# amplifier_v0001.net
KiCad netlist of a schematic drawn in EAGLE
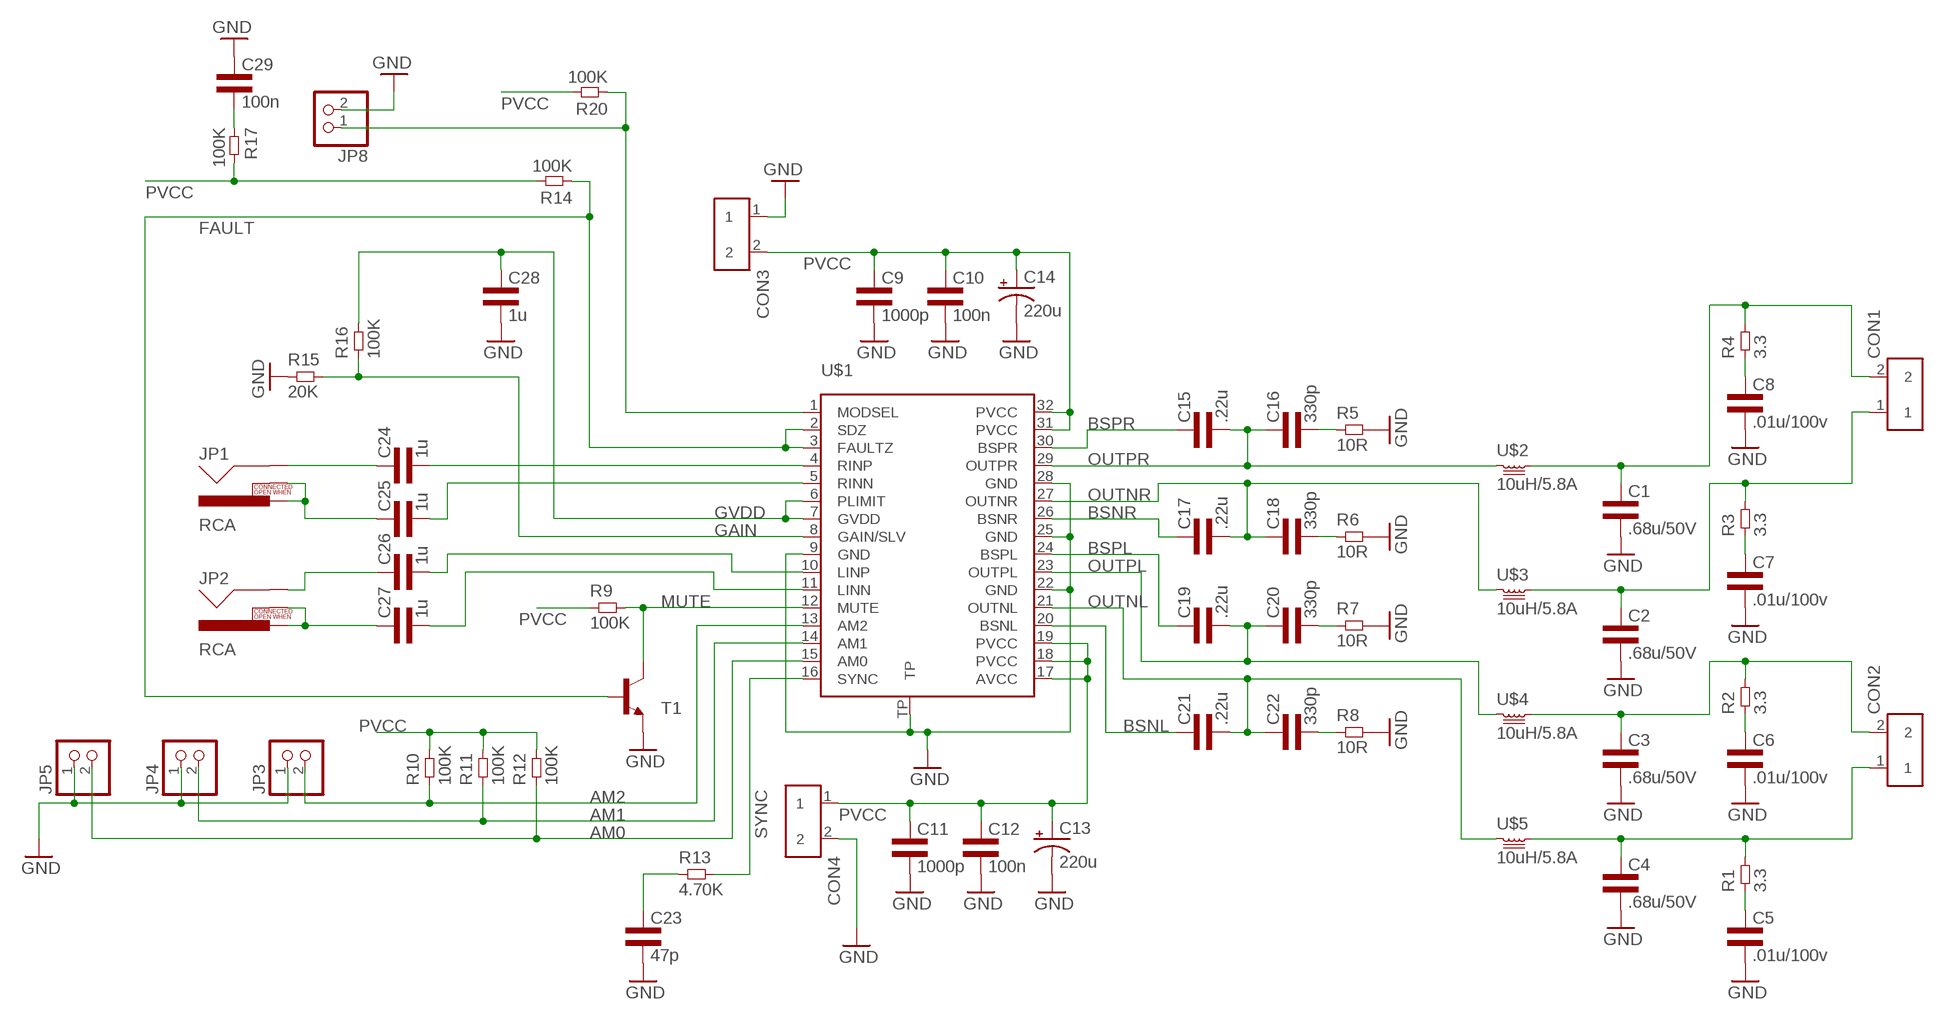
[diagram p0: schematic, sheet 1]

(export (version "E")
  (design (tool "Eeschema 10.0.6"))
  (components
    (comp (ref "C1")
      (value ".68u/50V")
      (footprint "eagle-import:1206L3")
      (libsource (lib "eagle-import") (part "CAP1206L3"))
    )
    (comp (ref "C2")
      (value ".68u/50V")
      (footprint "eagle-import:1206L3")
      (libsource (lib "eagle-import") (part "CAP1206L3"))
    )
    (comp (ref "C3")
      (value ".68u/50V")
      (footprint "eagle-import:1206L3")
      (libsource (lib "eagle-import") (part "CAP1206L3"))
    )
    (comp (ref "C4")
      (value ".68u/50V")
      (footprint "eagle-import:1206L3")
      (libsource (lib "eagle-import") (part "CAP1206L3"))
    )
    (comp (ref "C5")
      (value ".01u/100v")
      (footprint "eagle-import:0805L3")
      (libsource (lib "eagle-import") (part "CAP0805L3"))
    )
    (comp (ref "C6")
      (value ".01u/100v")
      (footprint "eagle-import:0805L3")
      (libsource (lib "eagle-import") (part "CAP0805L3"))
    )
    (comp (ref "C7")
      (value ".01u/100v")
      (footprint "eagle-import:0805L3")
      (libsource (lib "eagle-import") (part "CAP0805L3"))
    )
    (comp (ref "C8")
      (value ".01u/100v")
      (footprint "eagle-import:0805L3")
      (libsource (lib "eagle-import") (part "CAP0805L3"))
    )
    (comp (ref "C9")
      (value "1000p")
      (footprint "eagle-import:0603L3")
      (libsource (lib "eagle-import") (part "CAP0603L3"))
    )
    (comp (ref "C10")
      (value "100n")
      (footprint "eagle-import:0603L3")
      (libsource (lib "eagle-import") (part "CAP0603L3"))
    )
    (comp (ref "C11")
      (value "1000p")
      (footprint "eagle-import:0603L3")
      (libsource (lib "eagle-import") (part "CAP0603L3"))
    )
    (comp (ref "C12")
      (value "100n")
      (footprint "eagle-import:0603L3")
      (libsource (lib "eagle-import") (part "CAP0603L3"))
    )
    (comp (ref "C13")
      (value "220u")
      (footprint "eagle-import:E3,5-8")
      (libsource (lib "eagle-import") (part "CPOL-USE3.5-8"))
    )
    (comp (ref "C14")
      (value "220u")
      (footprint "eagle-import:E3,5-8")
      (libsource (lib "eagle-import") (part "CPOL-USE3.5-8"))
    )
    (comp (ref "C15")
      (value ".22u")
      (footprint "eagle-import:0603L3")
      (libsource (lib "eagle-import") (part "CAP0603L3"))
    )
    (comp (ref "C16")
      (value "330p")
      (footprint "eagle-import:0603L3")
      (libsource (lib "eagle-import") (part "CAP0603L3"))
    )
    (comp (ref "C17")
      (value ".22u")
      (footprint "eagle-import:0603L3")
      (libsource (lib "eagle-import") (part "CAP0603L3"))
    )
    (comp (ref "C18")
      (value "330p")
      (footprint "eagle-import:0603L3")
      (libsource (lib "eagle-import") (part "CAP0603L3"))
    )
    (comp (ref "C19")
      (value ".22u")
      (footprint "eagle-import:0603L3")
      (libsource (lib "eagle-import") (part "CAP0603L3"))
    )
    (comp (ref "C20")
      (value "330p")
      (footprint "eagle-import:0603L3")
      (libsource (lib "eagle-import") (part "CAP0603L3"))
    )
    (comp (ref "C21")
      (value ".22u")
      (footprint "eagle-import:0603L3")
      (libsource (lib "eagle-import") (part "CAP0603L3"))
    )
    (comp (ref "C22")
      (value "330p")
      (footprint "eagle-import:0603L3")
      (libsource (lib "eagle-import") (part "CAP0603L3"))
    )
    (comp (ref "C23")
      (value "47p")
      (footprint "eagle-import:0603L3")
      (libsource (lib "eagle-import") (part "CAP0603L3"))
    )
    (comp (ref "C24")
      (value "1u")
      (footprint "eagle-import:0603L3")
      (libsource (lib "eagle-import") (part "CAP0603L3"))
    )
    (comp (ref "C25")
      (value "1u")
      (footprint "eagle-import:0603L3")
      (libsource (lib "eagle-import") (part "CAP0603L3"))
    )
    (comp (ref "C26")
      (value "1u")
      (footprint "eagle-import:0603L3")
      (libsource (lib "eagle-import") (part "CAP0603L3"))
    )
    (comp (ref "C27")
      (value "1u")
      (footprint "eagle-import:0603L3")
      (libsource (lib "eagle-import") (part "CAP0603L3"))
    )
    (comp (ref "C28")
      (value "1u")
      (footprint "eagle-import:0603L3")
      (libsource (lib "eagle-import") (part "CAP0603L3"))
    )
    (comp (ref "C29")
      (value "100n")
      (footprint "eagle-import:0603L3")
      (libsource (lib "eagle-import") (part "CAP0603L3"))
    )
    (comp (ref "CON1")
      (value "TERM_BLOCK_2")
      (footprint "eagle-import:TERM_BLOCK_2")
      (libsource (lib "eagle-import") (part "TERM_BLOCK_2"))
    )
    (comp (ref "CON2")
      (value "TERM_BLOCK_2")
      (footprint "eagle-import:TERM_BLOCK_2")
      (libsource (lib "eagle-import") (part "TERM_BLOCK_2"))
    )
    (comp (ref "CON3")
      (value "TERM_BLOCK_2")
      (footprint "eagle-import:TERM_BLOCK_2")
      (libsource (lib "eagle-import") (part "TERM_BLOCK_2"))
    )
    (comp (ref "CON4")
      (value "TERM_BLOCK_2")
      (footprint "eagle-import:TERM_BLOCK_2")
      (libsource (lib "eagle-import") (part "TERM_BLOCK_2"))
    )
    (comp (ref "JP1")
      (value "RCA")
      (footprint "eagle-import:RCA")
      (libsource (lib "eagle-import") (part "RCA"))
    )
    (comp (ref "JP2")
      (value "RCA")
      (footprint "eagle-import:RCA")
      (libsource (lib "eagle-import") (part "RCA"))
    )
    (comp (ref "JP3")
      (value "PINHD-1X2")
      (footprint "eagle-import:1X02")
      (libsource (lib "eagle-import") (part "PINHD-1X2"))
    )
    (comp (ref "JP4")
      (value "PINHD-1X2")
      (footprint "eagle-import:1X02")
      (libsource (lib "eagle-import") (part "PINHD-1X2"))
    )
    (comp (ref "JP5")
      (value "PINHD-1X2")
      (footprint "eagle-import:1X02")
      (libsource (lib "eagle-import") (part "PINHD-1X2"))
    )
    (comp (ref "JP8")
      (value "PINHD-1X2")
      (footprint "eagle-import:1X02")
      (libsource (lib "eagle-import") (part "PINHD-1X2"))
    )
    (comp (ref "R1")
      (value "3.3")
      (footprint "eagle-import:0603L3")
      (libsource (lib "eagle-import") (part "RES0603L3"))
    )
    (comp (ref "R2")
      (value "3.3")
      (footprint "eagle-import:0603L3")
      (libsource (lib "eagle-import") (part "RES0603L3"))
    )
    (comp (ref "R3")
      (value "3.3")
      (footprint "eagle-import:0603L3")
      (libsource (lib "eagle-import") (part "RES0603L3"))
    )
    (comp (ref "R4")
      (value "3.3")
      (footprint "eagle-import:0603L3")
      (libsource (lib "eagle-import") (part "RES0603L3"))
    )
    (comp (ref "R5")
      (value "10R")
      (footprint "eagle-import:0805L3")
      (libsource (lib "eagle-import") (part "RES0805L3"))
    )
    (comp (ref "R6")
      (value "10R")
      (footprint "eagle-import:0805L3")
      (libsource (lib "eagle-import") (part "RES0805L3"))
    )
    (comp (ref "R7")
      (value "10R")
      (footprint "eagle-import:0805L3")
      (libsource (lib "eagle-import") (part "RES0805L3"))
    )
    (comp (ref "R8")
      (value "10R")
      (footprint "eagle-import:0805L3")
      (libsource (lib "eagle-import") (part "RES0805L3"))
    )
    (comp (ref "R9")
      (value "100K")
      (footprint "eagle-import:0603L3")
      (libsource (lib "eagle-import") (part "RES0603L3"))
    )
    (comp (ref "R10")
      (value "100K")
      (footprint "eagle-import:0603L3")
      (libsource (lib "eagle-import") (part "RES0603L3"))
    )
    (comp (ref "R11")
      (value "100K")
      (footprint "eagle-import:0603L3")
      (libsource (lib "eagle-import") (part "RES0603L3"))
    )
    (comp (ref "R12")
      (value "100K")
      (footprint "eagle-import:0603L3")
      (libsource (lib "eagle-import") (part "RES0603L3"))
    )
    (comp (ref "R13")
      (value "4.70K")
      (footprint "eagle-import:0603L3")
      (libsource (lib "eagle-import") (part "RES0603L3"))
    )
    (comp (ref "R14")
      (value "100K")
      (footprint "eagle-import:0603L3")
      (libsource (lib "eagle-import") (part "RES0603L3"))
    )
    (comp (ref "R15")
      (value "20K")
      (footprint "eagle-import:0603L3")
      (libsource (lib "eagle-import") (part "RES0603L3"))
    )
    (comp (ref "R16")
      (value "100K")
      (footprint "eagle-import:0603L3")
      (libsource (lib "eagle-import") (part "RES0603L3"))
    )
    (comp (ref "R17")
      (value "100K")
      (footprint "eagle-import:0603L3")
      (libsource (lib "eagle-import") (part "RES0603L3"))
    )
    (comp (ref "R20")
      (value "100K")
      (footprint "eagle-import:0603L3")
      (libsource (lib "eagle-import") (part "RES0603L3"))
    )
    (comp (ref "T1")
      (value "TRANSISTOR_MMBT2222ALT1-NPN-SOT23-BEC")
      (footprint "eagle-import:TRANSISTOR_SOT23-BEC")
      (libsource (lib "eagle-import") (part "TRANSISTOR_-NPN-SOT23-BECMMBT2222ALT1"))
    )
    (comp (ref "U$1")
      (value "TPA3116")
      (footprint "eagle-import:R-PDSO-32")
      (libsource (lib "eagle-import") (part "TPA3116"))
    )
    (comp (ref "U$2")
      (value "10uH/5.8A")
      (footprint "eagle-import:DR127")
      (libsource (lib "eagle-import") (part "INDUCTORDR127"))
    )
    (comp (ref "U$3")
      (value "10uH/5.8A")
      (footprint "eagle-import:DR127")
      (libsource (lib "eagle-import") (part "INDUCTORDR127"))
    )
    (comp (ref "U$4")
      (value "10uH/5.8A")
      (footprint "eagle-import:DR127")
      (libsource (lib "eagle-import") (part "INDUCTORDR127"))
    )
    (comp (ref "U$5")
      (value "10uH/5.8A")
      (footprint "eagle-import:DR127")
      (libsource (lib "eagle-import") (part "INDUCTORDR127"))
    )
  )
  (nets
    (net (code "1") (name "/AM0") (class "Default")
      (node (ref "JP5") (pin "2") (pinfunction "2_2") (pintype "passive"))
      (node (ref "R12") (pin "P$1") (pinfunction "1_P$1") (pintype "bidirectional"))
      (node (ref "U$1") (pin "15") (pinfunction "AM0_15") (pintype "bidirectional"))
    )
    (net (code "2") (name "/AM1") (class "Default")
      (node (ref "JP4") (pin "2") (pinfunction "2_2") (pintype "passive"))
      (node (ref "R11") (pin "P$1") (pinfunction "1_P$1") (pintype "bidirectional"))
      (node (ref "U$1") (pin "14") (pinfunction "AM1_14") (pintype "bidirectional"))
    )
    (net (code "3") (name "/AM2") (class "Default")
      (node (ref "JP3") (pin "2") (pinfunction "2_2") (pintype "passive"))
      (node (ref "R10") (pin "P$1") (pinfunction "1_P$1") (pintype "bidirectional"))
      (node (ref "U$1") (pin "13") (pinfunction "AM2_13") (pintype "bidirectional"))
    )
    (net (code "4") (name "/BSNL") (class "Default")
      (node (ref "C21") (pin "P$1") (pinfunction "1_P$1") (pintype "bidirectional"))
      (node (ref "U$1") (pin "20") (pinfunction "BSNL_20") (pintype "bidirectional"))
    )
    (net (code "5") (name "/BSNR") (class "Default")
      (node (ref "C17") (pin "P$1") (pinfunction "1_P$1") (pintype "bidirectional"))
      (node (ref "U$1") (pin "26") (pinfunction "BSNR_26") (pintype "bidirectional"))
    )
    (net (code "6") (name "/BSPL") (class "Default")
      (node (ref "C19") (pin "P$1") (pinfunction "1_P$1") (pintype "bidirectional"))
      (node (ref "U$1") (pin "24") (pinfunction "BSPL_24") (pintype "bidirectional"))
    )
    (net (code "7") (name "/BSPR") (class "Default")
      (node (ref "C15") (pin "P$1") (pinfunction "1_P$1") (pintype "bidirectional"))
      (node (ref "U$1") (pin "30") (pinfunction "BSPR_30") (pintype "bidirectional"))
    )
    (net (code "8") (name "/FAULT") (class "Default")
      (node (ref "R14") (pin "P$1") (pinfunction "1_P$1") (pintype "bidirectional"))
      (node (ref "T1") (pin "B") (pinfunction "B_B") (pintype "passive"))
      (node (ref "U$1") (pin "2") (pinfunction "SDZ_2") (pintype "bidirectional"))
      (node (ref "U$1") (pin "3") (pinfunction "FAULTZ_3") (pintype "bidirectional"))
    )
    (net (code "9") (name "/GAIN") (class "Default")
      (node (ref "R15") (pin "P$2") (pinfunction "2_P$2") (pintype "bidirectional"))
      (node (ref "R16") (pin "P$1") (pinfunction "1_P$1") (pintype "bidirectional"))
      (node (ref "U$1") (pin "8") (pinfunction "GAIN/SLV_8") (pintype "bidirectional"))
    )
    (net (code "10") (name "/GVDD") (class "Default")
      (node (ref "C28") (pin "P$1") (pinfunction "1_P$1") (pintype "bidirectional"))
      (node (ref "R16") (pin "P$2") (pinfunction "2_P$2") (pintype "bidirectional"))
      (node (ref "U$1") (pin "6") (pinfunction "PLIMIT_6") (pintype "bidirectional"))
      (node (ref "U$1") (pin "7") (pinfunction "GVDD_7") (pintype "bidirectional"))
    )
    (net (code "11") (name "/MUTE") (class "Default")
      (node (ref "R9") (pin "P$2") (pinfunction "2_P$2") (pintype "bidirectional"))
      (node (ref "T1") (pin "C") (pinfunction "C_C") (pintype "passive"))
      (node (ref "U$1") (pin "12") (pinfunction "MUTE_12") (pintype "bidirectional"))
    )
    (net (code "12") (name "/OUTNL") (class "Default")
      (node (ref "C21") (pin "P$2") (pinfunction "2_P$2") (pintype "bidirectional"))
      (node (ref "C22") (pin "P$1") (pinfunction "1_P$1") (pintype "bidirectional"))
      (node (ref "U$1") (pin "21") (pinfunction "OUTNL_21") (pintype "bidirectional"))
      (node (ref "U$5") (pin "1") (pinfunction "1_1") (pintype "bidirectional"))
    )
    (net (code "13") (name "/OUTNR") (class "Default")
      (node (ref "C17") (pin "P$2") (pinfunction "2_P$2") (pintype "bidirectional"))
      (node (ref "C18") (pin "P$1") (pinfunction "1_P$1") (pintype "bidirectional"))
      (node (ref "U$1") (pin "27") (pinfunction "OUTNR_27") (pintype "bidirectional"))
      (node (ref "U$3") (pin "1") (pinfunction "1_1") (pintype "bidirectional"))
    )
    (net (code "14") (name "/OUTPL") (class "Default")
      (node (ref "C19") (pin "P$2") (pinfunction "2_P$2") (pintype "bidirectional"))
      (node (ref "C20") (pin "P$1") (pinfunction "1_P$1") (pintype "bidirectional"))
      (node (ref "U$1") (pin "23") (pinfunction "OUTPL_23") (pintype "bidirectional"))
      (node (ref "U$4") (pin "1") (pinfunction "1_1") (pintype "bidirectional"))
    )
    (net (code "15") (name "/OUTPR") (class "Default")
      (node (ref "C15") (pin "P$2") (pinfunction "2_P$2") (pintype "bidirectional"))
      (node (ref "C16") (pin "P$1") (pinfunction "1_P$1") (pintype "bidirectional"))
      (node (ref "U$1") (pin "29") (pinfunction "OUTPR_29") (pintype "bidirectional"))
      (node (ref "U$2") (pin "1") (pinfunction "1_1") (pintype "bidirectional"))
    )
    (net (code "16") (name "/PVCC") (class "Default")
      (node (ref "C10") (pin "P$1") (pinfunction "1_P$1") (pintype "bidirectional"))
      (node (ref "C11") (pin "P$1") (pinfunction "1_P$1") (pintype "bidirectional"))
      (node (ref "C12") (pin "P$1") (pinfunction "1_P$1") (pintype "bidirectional"))
      (node (ref "C13") (pin "+") (pinfunction "+_+") (pintype "passive"))
      (node (ref "C14") (pin "+") (pinfunction "+_+") (pintype "passive"))
      (node (ref "C9") (pin "P$1") (pinfunction "1_P$1") (pintype "bidirectional"))
      (node (ref "CON3") (pin "2") (pinfunction "2_2") (pintype "bidirectional"))
      (node (ref "CON4") (pin "1") (pinfunction "1_1") (pintype "bidirectional"))
      (node (ref "R10") (pin "P$2") (pinfunction "2_P$2") (pintype "bidirectional"))
      (node (ref "R11") (pin "P$2") (pinfunction "2_P$2") (pintype "bidirectional"))
      (node (ref "R12") (pin "P$2") (pinfunction "2_P$2") (pintype "bidirectional"))
      (node (ref "R14") (pin "P$2") (pinfunction "2_P$2") (pintype "bidirectional"))
      (node (ref "R17") (pin "P$2") (pinfunction "2_P$2") (pintype "bidirectional"))
      (node (ref "R20") (pin "P$2") (pinfunction "2_P$2") (pintype "bidirectional"))
      (node (ref "R9") (pin "P$1") (pinfunction "1_P$1") (pintype "bidirectional"))
      (node (ref "U$1") (pin "17") (pinfunction "AVCC_17") (pintype "bidirectional"))
      (node (ref "U$1") (pin "18") (pinfunction "PVCC_18") (pintype "bidirectional"))
      (node (ref "U$1") (pin "19") (pinfunction "PVCC_19") (pintype "bidirectional"))
      (node (ref "U$1") (pin "31") (pinfunction "PVCC_31") (pintype "bidirectional"))
      (node (ref "U$1") (pin "32") (pinfunction "PVCC_32") (pintype "bidirectional"))
    )
    (net (code "17") (name "/SYNC") (class "Default")
      (node (ref "R13") (pin "P$2") (pinfunction "2_P$2") (pintype "bidirectional"))
      (node (ref "U$1") (pin "16") (pinfunction "SYNC_16") (pintype "bidirectional"))
    )
    (net (code "18") (name "GND") (class "Default")
      (node (ref "C1") (pin "2") (pinfunction "2_2") (pintype "bidirectional"))
      (node (ref "C10") (pin "P$2") (pinfunction "2_P$2") (pintype "bidirectional"))
      (node (ref "C11") (pin "P$2") (pinfunction "2_P$2") (pintype "bidirectional"))
      (node (ref "C12") (pin "P$2") (pinfunction "2_P$2") (pintype "bidirectional"))
      (node (ref "C13") (pin "-") (pinfunction "-_-") (pintype "passive"))
      (node (ref "C14") (pin "-") (pinfunction "-_-") (pintype "passive"))
      (node (ref "C2") (pin "2") (pinfunction "2_2") (pintype "bidirectional"))
      (node (ref "C23") (pin "P$2") (pinfunction "2_P$2") (pintype "bidirectional"))
      (node (ref "C28") (pin "P$2") (pinfunction "2_P$2") (pintype "bidirectional"))
      (node (ref "C29") (pin "P$1") (pinfunction "1_P$1") (pintype "bidirectional"))
      (node (ref "C3") (pin "2") (pinfunction "2_2") (pintype "bidirectional"))
      (node (ref "C4") (pin "2") (pinfunction "2_2") (pintype "bidirectional"))
      (node (ref "C5") (pin "2") (pinfunction "2_2") (pintype "bidirectional"))
      (node (ref "C6") (pin "2") (pinfunction "2_2") (pintype "bidirectional"))
      (node (ref "C7") (pin "2") (pinfunction "2_2") (pintype "bidirectional"))
      (node (ref "C8") (pin "2") (pinfunction "2_2") (pintype "bidirectional"))
      (node (ref "C9") (pin "P$2") (pinfunction "2_P$2") (pintype "bidirectional"))
      (node (ref "CON3") (pin "1") (pinfunction "1_1") (pintype "bidirectional"))
      (node (ref "CON4") (pin "2") (pinfunction "2_2") (pintype "bidirectional"))
      (node (ref "JP3") (pin "1") (pinfunction "1_1") (pintype "passive"))
      (node (ref "JP4") (pin "1") (pinfunction "1_1") (pintype "passive"))
      (node (ref "JP5") (pin "1") (pinfunction "1_1") (pintype "passive"))
      (node (ref "JP8") (pin "2") (pinfunction "2_2") (pintype "passive"))
      (node (ref "R15") (pin "P$1") (pinfunction "1_P$1") (pintype "bidirectional"))
      (node (ref "R5") (pin "2") (pinfunction "2_2") (pintype "bidirectional"))
      (node (ref "R6") (pin "2") (pinfunction "2_2") (pintype "bidirectional"))
      (node (ref "R7") (pin "2") (pinfunction "2_2") (pintype "bidirectional"))
      (node (ref "R8") (pin "2") (pinfunction "2_2") (pintype "bidirectional"))
      (node (ref "T1") (pin "E") (pinfunction "E_E") (pintype "passive"))
      (node (ref "U$1") (pin "22") (pinfunction "GND_22") (pintype "bidirectional"))
      (node (ref "U$1") (pin "25") (pinfunction "GND_25") (pintype "bidirectional"))
      (node (ref "U$1") (pin "28") (pinfunction "GND_28") (pintype "bidirectional"))
      (node (ref "U$1") (pin "9") (pinfunction "GND_9") (pintype "bidirectional"))
      (node (ref "U$1") (pin "TP") (pinfunction "TP_TP") (pintype "bidirectional"))
    )
    (net (code "19") (name "Net-(C16-2)") (class "Default")
      (node (ref "C16") (pin "P$2") (pinfunction "2_P$2") (pintype "bidirectional"))
      (node (ref "R5") (pin "1") (pinfunction "1_1") (pintype "bidirectional"))
    )
    (net (code "20") (name "Net-(C18-2)") (class "Default")
      (node (ref "C18") (pin "P$2") (pinfunction "2_P$2") (pintype "bidirectional"))
      (node (ref "R6") (pin "1") (pinfunction "1_1") (pintype "bidirectional"))
    )
    (net (code "21") (name "Net-(C20-2)") (class "Default")
      (node (ref "C20") (pin "P$2") (pinfunction "2_P$2") (pintype "bidirectional"))
      (node (ref "R7") (pin "1") (pinfunction "1_1") (pintype "bidirectional"))
    )
    (net (code "22") (name "Net-(C22-2)") (class "Default")
      (node (ref "C22") (pin "P$2") (pinfunction "2_P$2") (pintype "bidirectional"))
      (node (ref "R8") (pin "1") (pinfunction "1_1") (pintype "bidirectional"))
    )
    (net (code "23") (name "Net-(C23-1)") (class "Default")
      (node (ref "C23") (pin "P$1") (pinfunction "1_P$1") (pintype "bidirectional"))
      (node (ref "R13") (pin "P$1") (pinfunction "1_P$1") (pintype "bidirectional"))
    )
    (net (code "24") (name "Net-(C24-1)") (class "Default")
      (node (ref "C24") (pin "P$1") (pinfunction "1_P$1") (pintype "bidirectional"))
      (node (ref "JP1") (pin "SHELL") (pinfunction "SHELL_SHELL") (pintype "bidirectional"))
    )
    (net (code "25") (name "Net-(C24-2)") (class "Default")
      (node (ref "C24") (pin "P$2") (pinfunction "2_P$2") (pintype "bidirectional"))
      (node (ref "U$1") (pin "4") (pinfunction "RINP_4") (pintype "bidirectional"))
    )
    (net (code "26") (name "Net-(C25-1)") (class "Default")
      (node (ref "C25") (pin "P$1") (pinfunction "1_P$1") (pintype "bidirectional"))
      (node (ref "JP1") (pin "PIN") (pinfunction "PIN_PIN") (pintype "bidirectional"))
      (node (ref "JP1") (pin "SWITCH") (pinfunction "SWITCH_SWITCH") (pintype "bidirectional"))
    )
    (net (code "27") (name "Net-(C25-2)") (class "Default")
      (node (ref "C25") (pin "P$2") (pinfunction "2_P$2") (pintype "bidirectional"))
      (node (ref "U$1") (pin "5") (pinfunction "RINN_5") (pintype "bidirectional"))
    )
    (net (code "28") (name "Net-(C26-1)") (class "Default")
      (node (ref "C26") (pin "P$1") (pinfunction "1_P$1") (pintype "bidirectional"))
      (node (ref "JP2") (pin "SHELL") (pinfunction "SHELL_SHELL") (pintype "bidirectional"))
    )
    (net (code "29") (name "Net-(C26-2)") (class "Default")
      (node (ref "C26") (pin "P$2") (pinfunction "2_P$2") (pintype "bidirectional"))
      (node (ref "U$1") (pin "10") (pinfunction "LINP_10") (pintype "bidirectional"))
    )
    (net (code "30") (name "Net-(C27-1)") (class "Default")
      (node (ref "C27") (pin "P$1") (pinfunction "1_P$1") (pintype "bidirectional"))
      (node (ref "JP2") (pin "PIN") (pinfunction "PIN_PIN") (pintype "bidirectional"))
      (node (ref "JP2") (pin "SWITCH") (pinfunction "SWITCH_SWITCH") (pintype "bidirectional"))
    )
    (net (code "31") (name "Net-(C27-2)") (class "Default")
      (node (ref "C27") (pin "P$2") (pinfunction "2_P$2") (pintype "bidirectional"))
      (node (ref "U$1") (pin "11") (pinfunction "LINN_11") (pintype "bidirectional"))
    )
    (net (code "32") (name "Net-(C29-2)") (class "Default")
      (node (ref "C29") (pin "P$2") (pinfunction "2_P$2") (pintype "bidirectional"))
      (node (ref "R17") (pin "P$1") (pinfunction "1_P$1") (pintype "bidirectional"))
    )
    (net (code "33") (name "Net-(R1-1)") (class "Default")
      (node (ref "C5") (pin "1") (pinfunction "1_1") (pintype "bidirectional"))
      (node (ref "R1") (pin "P$1") (pinfunction "1_P$1") (pintype "bidirectional"))
    )
    (net (code "34") (name "Net-(R1-2)") (class "Default")
      (node (ref "C4") (pin "1") (pinfunction "1_1") (pintype "bidirectional"))
      (node (ref "CON2") (pin "1") (pinfunction "1_1") (pintype "bidirectional"))
      (node (ref "R1") (pin "P$2") (pinfunction "2_P$2") (pintype "bidirectional"))
      (node (ref "U$5") (pin "2") (pinfunction "2_2") (pintype "bidirectional"))
    )
    (net (code "35") (name "Net-(R2-1)") (class "Default")
      (node (ref "C6") (pin "1") (pinfunction "1_1") (pintype "bidirectional"))
      (node (ref "R2") (pin "P$1") (pinfunction "1_P$1") (pintype "bidirectional"))
    )
    (net (code "36") (name "Net-(R2-2)") (class "Default")
      (node (ref "C3") (pin "1") (pinfunction "1_1") (pintype "bidirectional"))
      (node (ref "CON2") (pin "2") (pinfunction "2_2") (pintype "bidirectional"))
      (node (ref "R2") (pin "P$2") (pinfunction "2_P$2") (pintype "bidirectional"))
      (node (ref "U$4") (pin "2") (pinfunction "2_2") (pintype "bidirectional"))
    )
    (net (code "37") (name "Net-(R3-1)") (class "Default")
      (node (ref "C7") (pin "1") (pinfunction "1_1") (pintype "bidirectional"))
      (node (ref "R3") (pin "P$1") (pinfunction "1_P$1") (pintype "bidirectional"))
    )
    (net (code "38") (name "Net-(R3-2)") (class "Default")
      (node (ref "C2") (pin "1") (pinfunction "1_1") (pintype "bidirectional"))
      (node (ref "CON1") (pin "1") (pinfunction "1_1") (pintype "bidirectional"))
      (node (ref "R3") (pin "P$2") (pinfunction "2_P$2") (pintype "bidirectional"))
      (node (ref "U$3") (pin "2") (pinfunction "2_2") (pintype "bidirectional"))
    )
    (net (code "39") (name "Net-(R4-1)") (class "Default")
      (node (ref "C8") (pin "1") (pinfunction "1_1") (pintype "bidirectional"))
      (node (ref "R4") (pin "P$1") (pinfunction "1_P$1") (pintype "bidirectional"))
    )
    (net (code "40") (name "Net-(R4-2)") (class "Default")
      (node (ref "C1") (pin "1") (pinfunction "1_1") (pintype "bidirectional"))
      (node (ref "CON1") (pin "2") (pinfunction "2_2") (pintype "bidirectional"))
      (node (ref "R4") (pin "P$2") (pinfunction "2_P$2") (pintype "bidirectional"))
      (node (ref "U$2") (pin "2") (pinfunction "2_2") (pintype "bidirectional"))
    )
    (net (code "41") (name "Net-(R20-1)") (class "Default")
      (node (ref "JP8") (pin "1") (pinfunction "1_1") (pintype "passive"))
      (node (ref "R20") (pin "P$1") (pinfunction "1_P$1") (pintype "bidirectional"))
      (node (ref "U$1") (pin "1") (pinfunction "MODSEL_1") (pintype "bidirectional"))
    )
  )
)
